# DDC112_Breadboard.net
KiCad netlist of a schematic drawn in Altium Designer
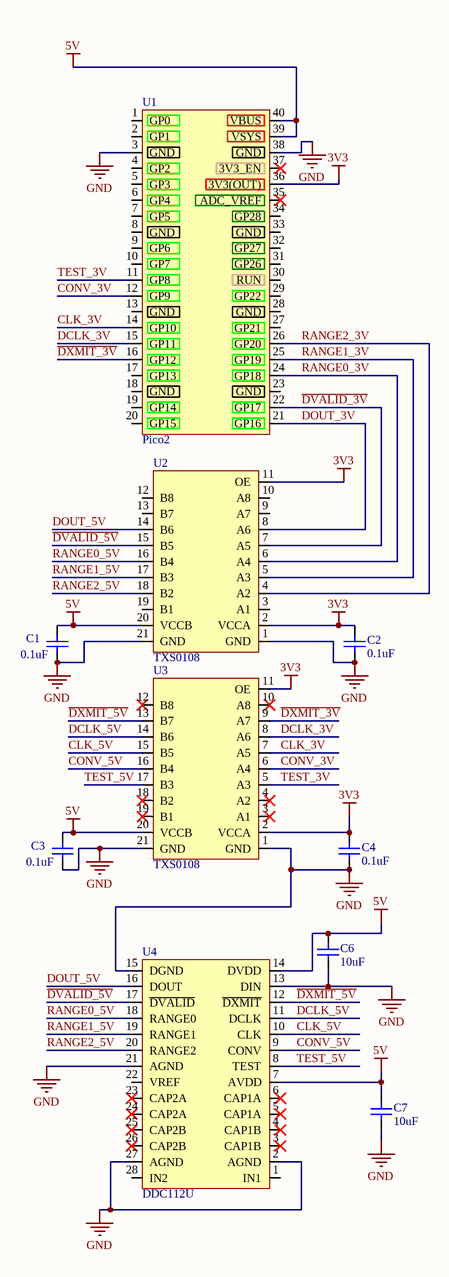
[diagram p0: DDC112_Breadboard.SchDoc]

(export (version "E")
  (design (tool "Eeschema 10.0.6"))
  (components
    (comp (ref "C1")
      (value "0.1uF")
      (description "Cap, Nonpolar, Any, Must choose footprint manually")
      (libsource (lib "DDC112_Components") (part "CAP"))
    )
    (comp (ref "C2")
      (value "0.1uF")
      (description "Cap, Nonpolar, Any, Must choose footprint manually")
      (libsource (lib "DDC112_Components") (part "CAP"))
    )
    (comp (ref "C3")
      (value "0.1uF")
      (description "Cap, Nonpolar, Any, Must choose footprint manually")
      (libsource (lib "DDC112_Components") (part "CAP"))
    )
    (comp (ref "C4")
      (value "0.1uF")
      (description "Cap, Nonpolar, Any, Must choose footprint manually")
      (libsource (lib "DDC112_Components") (part "CAP"))
    )
    (comp (ref "C6")
      (value "10uF")
      (description "Cap, Nonpolar, Any, Must choose footprint manually")
      (libsource (lib "DDC112_Components") (part "CAP"))
    )
    (comp (ref "C7")
      (value "10uF")
      (description "Cap, Nonpolar, Any, Must choose footprint manually")
      (libsource (lib "DDC112_Components") (part "CAP"))
    )
    (comp (ref "U1")
      (value "Pico2")
      (description "Raspberry Pi RP2350 Board 40DIP")
      (libsource (lib "DDC112_Components") (part "Pico2"))
    )
    (comp (ref "U2") (value "TXS0108") (libsource (lib "DDC112_Components") (part "TXS0108")))
    (comp (ref "U3") (value "TXS0108") (libsource (lib "DDC112_Components") (part "TXS0108")))
    (comp (ref "U4")
      (value "DDC112U")
      (description "Dual Current Input 20-Bit ADC 28SOIC")
      (libsource (lib "DDC112_Components") (part "DDC112U"))
    )
  )
  (nets
    (net (code "1") (name "/CLK_3V") (class "Default")
      (node (ref "U1") (pin "14") (pinfunction "GP10_14") (pintype "passive"))
      (node (ref "U3") (pin "7") (pinfunction "A5_7") (pintype "passive"))
    )
    (net (code "2") (name "/CLK_5V") (class "Default")
      (node (ref "U3") (pin "15") (pinfunction "B5_15") (pintype "passive"))
      (node (ref "U4") (pin "10") (pinfunction "CLK_10") (pintype "passive"))
    )
    (net (code "3") (name "/CONV_3V") (class "Default")
      (node (ref "U1") (pin "12") (pinfunction "GP9_12") (pintype "passive"))
      (node (ref "U3") (pin "6") (pinfunction "A4_6") (pintype "passive"))
    )
    (net (code "4") (name "/CONV_5V") (class "Default")
      (node (ref "U3") (pin "16") (pinfunction "B4_16") (pintype "passive"))
      (node (ref "U4") (pin "9") (pinfunction "CONV_9") (pintype "passive"))
    )
    (net (code "5") (name "/DCLK_3V") (class "Default")
      (node (ref "U1") (pin "15") (pinfunction "GP11_15") (pintype "passive"))
      (node (ref "U3") (pin "8") (pinfunction "A6_8") (pintype "passive"))
    )
    (net (code "6") (name "/DCLK_5V") (class "Default")
      (node (ref "U3") (pin "14") (pinfunction "B6_14") (pintype "passive"))
      (node (ref "U4") (pin "11") (pinfunction "DCLK_11") (pintype "passive"))
    )
    (net (code "7") (name "/DOUT_3V") (class "Default")
      (node (ref "U1") (pin "21") (pinfunction "GP16_21") (pintype "passive"))
      (node (ref "U2") (pin "8") (pinfunction "A6_8") (pintype "passive"))
    )
    (net (code "8") (name "/DOUT_5V") (class "Default")
      (node (ref "U2") (pin "14") (pinfunction "B6_14") (pintype "passive"))
      (node (ref "U4") (pin "16") (pinfunction "DOUT_16") (pintype "passive"))
    )
    (net (code "9") (name "/DVALID_3V") (class "Default")
      (node (ref "U1") (pin "22") (pinfunction "GP17_22") (pintype "passive"))
      (node (ref "U2") (pin "7") (pinfunction "A5_7") (pintype "passive"))
    )
    (net (code "10") (name "/DVALID_5V") (class "Default")
      (node (ref "U2") (pin "15") (pinfunction "B5_15") (pintype "passive"))
      (node (ref "U4") (pin "17") (pinfunction "~{DVALID}_17") (pintype "passive"))
    )
    (net (code "11") (name "/DXMIT_3V") (class "Default")
      (node (ref "U1") (pin "16") (pinfunction "GP12_16") (pintype "passive"))
      (node (ref "U3") (pin "9") (pinfunction "A7_9") (pintype "passive"))
    )
    (net (code "12") (name "/DXMIT_5V") (class "Default")
      (node (ref "U3") (pin "13") (pinfunction "B7_13") (pintype "passive"))
      (node (ref "U4") (pin "12") (pinfunction "~{DXMIT}_12") (pintype "passive"))
    )
    (net (code "13") (name "/RANGE0_3V") (class "Default")
      (node (ref "U1") (pin "24") (pinfunction "GP18_24") (pintype "passive"))
      (node (ref "U2") (pin "6") (pinfunction "A4_6") (pintype "passive"))
    )
    (net (code "14") (name "/RANGE0_5V") (class "Default")
      (node (ref "U2") (pin "16") (pinfunction "B4_16") (pintype "passive"))
      (node (ref "U4") (pin "18") (pinfunction "RANGE0_18") (pintype "passive"))
    )
    (net (code "15") (name "/RANGE1_3V") (class "Default")
      (node (ref "U1") (pin "25") (pinfunction "GP19_25") (pintype "passive"))
      (node (ref "U2") (pin "5") (pinfunction "A3_5") (pintype "passive"))
    )
    (net (code "16") (name "/RANGE1_5V") (class "Default")
      (node (ref "U2") (pin "17") (pinfunction "B3_17") (pintype "passive"))
      (node (ref "U4") (pin "19") (pinfunction "RANGE1_19") (pintype "passive"))
    )
    (net (code "17") (name "/RANGE2_3V") (class "Default")
      (node (ref "U1") (pin "26") (pinfunction "GP20_26") (pintype "passive"))
      (node (ref "U2") (pin "4") (pinfunction "A2_4") (pintype "passive"))
    )
    (net (code "18") (name "/RANGE2_5V") (class "Default")
      (node (ref "U2") (pin "18") (pinfunction "B2_18") (pintype "passive"))
      (node (ref "U4") (pin "20") (pinfunction "RANGE2_20") (pintype "passive"))
    )
    (net (code "19") (name "/TEST_3V") (class "Default")
      (node (ref "U1") (pin "11") (pinfunction "GP8_11") (pintype "passive"))
      (node (ref "U3") (pin "5") (pinfunction "A3_5") (pintype "passive"))
    )
    (net (code "20") (name "/TEST_5V") (class "Default")
      (node (ref "U3") (pin "17") (pinfunction "B3_17") (pintype "passive"))
      (node (ref "U4") (pin "8") (pinfunction "TEST_8") (pintype "passive"))
    )
    (net (code "21") (name "3V3") (class "Default")
      (node (ref "C2") (pin "1") (pinfunction "1_1") (pintype "passive"))
      (node (ref "C4") (pin "1") (pinfunction "1_1") (pintype "passive"))
      (node (ref "U1") (pin "36") (pinfunction "3V3(OUT)_36") (pintype "passive"))
      (node (ref "U2") (pin "11") (pinfunction "OE_11") (pintype "passive"))
      (node (ref "U2") (pin "2") (pinfunction "VCCA_2") (pintype "passive"))
      (node (ref "U3") (pin "11") (pinfunction "OE_11") (pintype "passive"))
      (node (ref "U3") (pin "2") (pinfunction "VCCA_2") (pintype "passive"))
    )
    (net (code "22") (name "5V") (class "Default")
      (node (ref "C1") (pin "1") (pinfunction "1_1") (pintype "passive"))
      (node (ref "C3") (pin "1") (pinfunction "1_1") (pintype "passive"))
      (node (ref "C6") (pin "1") (pinfunction "1_1") (pintype "passive"))
      (node (ref "C7") (pin "1") (pinfunction "1_1") (pintype "passive"))
      (node (ref "U1") (pin "39") (pinfunction "VSYS_39") (pintype "passive"))
      (node (ref "U1") (pin "40") (pinfunction "VBUS_40") (pintype "passive"))
      (node (ref "U2") (pin "20") (pinfunction "VCCB_20") (pintype "passive"))
      (node (ref "U3") (pin "20") (pinfunction "VCCB_20") (pintype "passive"))
      (node (ref "U4") (pin "14") (pinfunction "DVDD_14") (pintype "passive"))
      (node (ref "U4") (pin "7") (pinfunction "AVDD_7") (pintype "passive"))
    )
    (net (code "23") (name "GND") (class "Default")
      (node (ref "C1") (pin "2") (pinfunction "2_2") (pintype "passive"))
      (node (ref "C2") (pin "2") (pinfunction "2_2") (pintype "passive"))
      (node (ref "C3") (pin "2") (pinfunction "2_2") (pintype "passive"))
      (node (ref "C4") (pin "2") (pinfunction "2_2") (pintype "passive"))
      (node (ref "C6") (pin "2") (pinfunction "2_2") (pintype "passive"))
      (node (ref "C7") (pin "2") (pinfunction "2_2") (pintype "passive"))
      (node (ref "U1") (pin "3") (pinfunction "GND_3") (pintype "passive"))
      (node (ref "U1") (pin "38") (pinfunction "GND_38") (pintype "passive"))
      (node (ref "U2") (pin "1") (pinfunction "GND_1") (pintype "passive"))
      (node (ref "U2") (pin "21") (pinfunction "GND_21") (pintype "passive"))
      (node (ref "U3") (pin "1") (pinfunction "GND_1") (pintype "passive"))
      (node (ref "U3") (pin "21") (pinfunction "GND_21") (pintype "passive"))
      (node (ref "U4") (pin "13") (pinfunction "DIN_13") (pintype "passive"))
      (node (ref "U4") (pin "15") (pinfunction "DGND_15") (pintype "passive"))
      (node (ref "U4") (pin "2") (pinfunction "AGND_2") (pintype "passive"))
      (node (ref "U4") (pin "21") (pinfunction "AGND_21") (pintype "passive"))
      (node (ref "U4") (pin "27") (pinfunction "AGND_27") (pintype "passive"))
    )
    (net (code "24") (name "unconnected-(U1-3V3_EN-Pad37)") (class "Default")
      (node (ref "U1") (pin "37") (pinfunction "3V3_EN_37") (pintype "passive+no_connect"))
    )
    (net (code "25") (name "unconnected-(U1-ADC_VREF-Pad35)") (class "Default")
      (node (ref "U1") (pin "35") (pinfunction "ADC_VREF_35") (pintype "passive+no_connect"))
    )
    (net (code "26") (name "unconnected-(U1-GND-Pad8)") (class "Default")
      (node (ref "U1") (pin "8") (pinfunction "GND_8") (pintype "passive"))
    )
    (net (code "27") (name "unconnected-(U1-GND-Pad13)") (class "Default")
      (node (ref "U1") (pin "13") (pinfunction "GND_13") (pintype "passive"))
    )
    (net (code "28") (name "unconnected-(U1-GND-Pad18)") (class "Default")
      (node (ref "U1") (pin "18") (pinfunction "GND_18") (pintype "passive"))
    )
    (net (code "29") (name "unconnected-(U1-GND-Pad23)") (class "Default")
      (node (ref "U1") (pin "23") (pinfunction "GND_23") (pintype "passive"))
    )
    (net (code "30") (name "unconnected-(U1-GND-Pad28)") (class "Default")
      (node (ref "U1") (pin "28") (pinfunction "GND_28") (pintype "passive"))
    )
    (net (code "31") (name "unconnected-(U1-GND-Pad33)") (class "Default")
      (node (ref "U1") (pin "33") (pinfunction "GND_33") (pintype "passive"))
    )
    (net (code "32") (name "unconnected-(U1-GP0-Pad1)") (class "Default")
      (node (ref "U1") (pin "1") (pinfunction "GP0_1") (pintype "passive"))
    )
    (net (code "33") (name "unconnected-(U1-GP1-Pad2)") (class "Default")
      (node (ref "U1") (pin "2") (pinfunction "GP1_2") (pintype "passive"))
    )
    (net (code "34") (name "unconnected-(U1-GP2-Pad4)") (class "Default")
      (node (ref "U1") (pin "4") (pinfunction "GP2_4") (pintype "passive"))
    )
    (net (code "35") (name "unconnected-(U1-GP3-Pad5)") (class "Default")
      (node (ref "U1") (pin "5") (pinfunction "GP3_5") (pintype "passive"))
    )
    (net (code "36") (name "unconnected-(U1-GP4-Pad6)") (class "Default")
      (node (ref "U1") (pin "6") (pinfunction "GP4_6") (pintype "passive"))
    )
    (net (code "37") (name "unconnected-(U1-GP5-Pad7)") (class "Default")
      (node (ref "U1") (pin "7") (pinfunction "GP5_7") (pintype "passive"))
    )
    (net (code "38") (name "unconnected-(U1-GP6-Pad9)") (class "Default")
      (node (ref "U1") (pin "9") (pinfunction "GP6_9") (pintype "passive"))
    )
    (net (code "39") (name "unconnected-(U1-GP7-Pad10)") (class "Default")
      (node (ref "U1") (pin "10") (pinfunction "GP7_10") (pintype "passive"))
    )
    (net (code "40") (name "unconnected-(U1-GP13-Pad17)") (class "Default")
      (node (ref "U1") (pin "17") (pinfunction "GP13_17") (pintype "passive"))
    )
    (net (code "41") (name "unconnected-(U1-GP14-Pad19)") (class "Default")
      (node (ref "U1") (pin "19") (pinfunction "GP14_19") (pintype "passive"))
    )
    (net (code "42") (name "unconnected-(U1-GP15-Pad20)") (class "Default")
      (node (ref "U1") (pin "20") (pinfunction "GP15_20") (pintype "passive"))
    )
    (net (code "43") (name "unconnected-(U1-GP21-Pad27)") (class "Default")
      (node (ref "U1") (pin "27") (pinfunction "GP21_27") (pintype "passive"))
    )
    (net (code "44") (name "unconnected-(U1-GP22-Pad29)") (class "Default")
      (node (ref "U1") (pin "29") (pinfunction "GP22_29") (pintype "passive"))
    )
    (net (code "45") (name "unconnected-(U1-GP26-Pad31)") (class "Default")
      (node (ref "U1") (pin "31") (pinfunction "GP26_31") (pintype "passive"))
    )
    (net (code "46") (name "unconnected-(U1-GP27-Pad32)") (class "Default")
      (node (ref "U1") (pin "32") (pinfunction "GP27_32") (pintype "passive"))
    )
    (net (code "47") (name "unconnected-(U1-GP28-Pad34)") (class "Default")
      (node (ref "U1") (pin "34") (pinfunction "GP28_34") (pintype "passive"))
    )
    (net (code "48") (name "unconnected-(U1-RUN-Pad30)") (class "Default")
      (node (ref "U1") (pin "30") (pinfunction "RUN_30") (pintype "passive"))
    )
    (net (code "49") (name "unconnected-(U2-A1-Pad3)") (class "Default")
      (node (ref "U2") (pin "3") (pinfunction "A1_3") (pintype "passive"))
    )
    (net (code "50") (name "unconnected-(U2-A7-Pad9)") (class "Default")
      (node (ref "U2") (pin "9") (pinfunction "A7_9") (pintype "passive"))
    )
    (net (code "51") (name "unconnected-(U2-A8-Pad10)") (class "Default")
      (node (ref "U2") (pin "10") (pinfunction "A8_10") (pintype "passive"))
    )
    (net (code "52") (name "unconnected-(U2-B1-Pad19)") (class "Default")
      (node (ref "U2") (pin "19") (pinfunction "B1_19") (pintype "passive"))
    )
    (net (code "53") (name "unconnected-(U2-B7-Pad13)") (class "Default")
      (node (ref "U2") (pin "13") (pinfunction "B7_13") (pintype "passive"))
    )
    (net (code "54") (name "unconnected-(U2-B8-Pad12)") (class "Default")
      (node (ref "U2") (pin "12") (pinfunction "B8_12") (pintype "passive"))
    )
    (net (code "55") (name "unconnected-(U3-A1-Pad3)") (class "Default")
      (node (ref "U3") (pin "3") (pinfunction "A1_3") (pintype "passive+no_connect"))
    )
    (net (code "56") (name "unconnected-(U3-A2-Pad4)") (class "Default")
      (node (ref "U3") (pin "4") (pinfunction "A2_4") (pintype "passive+no_connect"))
    )
    (net (code "57") (name "unconnected-(U3-A8-Pad10)") (class "Default")
      (node (ref "U3") (pin "10") (pinfunction "A8_10") (pintype "passive+no_connect"))
    )
    (net (code "58") (name "unconnected-(U3-B1-Pad19)") (class "Default")
      (node (ref "U3") (pin "19") (pinfunction "B1_19") (pintype "passive+no_connect"))
    )
    (net (code "59") (name "unconnected-(U3-B2-Pad18)") (class "Default")
      (node (ref "U3") (pin "18") (pinfunction "B2_18") (pintype "passive+no_connect"))
    )
    (net (code "60") (name "unconnected-(U3-B8-Pad12)") (class "Default")
      (node (ref "U3") (pin "12") (pinfunction "B8_12") (pintype "passive+no_connect"))
    )
    (net (code "61") (name "unconnected-(U4-CAP1A-Pad5)") (class "Default")
      (node (ref "U4") (pin "5") (pinfunction "CAP1A_5") (pintype "passive+no_connect"))
    )
    (net (code "62") (name "unconnected-(U4-CAP1A-Pad6)") (class "Default")
      (node (ref "U4") (pin "6") (pinfunction "CAP1A_6") (pintype "passive+no_connect"))
    )
    (net (code "63") (name "unconnected-(U4-CAP1B-Pad3)") (class "Default")
      (node (ref "U4") (pin "3") (pinfunction "CAP1B_3") (pintype "passive+no_connect"))
    )
    (net (code "64") (name "unconnected-(U4-CAP1B-Pad4)") (class "Default")
      (node (ref "U4") (pin "4") (pinfunction "CAP1B_4") (pintype "passive+no_connect"))
    )
    (net (code "65") (name "unconnected-(U4-CAP2A-Pad23)") (class "Default")
      (node (ref "U4") (pin "23") (pinfunction "CAP2A_23") (pintype "passive+no_connect"))
    )
    (net (code "66") (name "unconnected-(U4-CAP2A-Pad24)") (class "Default")
      (node (ref "U4") (pin "24") (pinfunction "CAP2A_24") (pintype "passive+no_connect"))
    )
    (net (code "67") (name "unconnected-(U4-CAP2B-Pad25)") (class "Default")
      (node (ref "U4") (pin "25") (pinfunction "CAP2B_25") (pintype "passive+no_connect"))
    )
    (net (code "68") (name "unconnected-(U4-CAP2B-Pad26)") (class "Default")
      (node (ref "U4") (pin "26") (pinfunction "CAP2B_26") (pintype "passive+no_connect"))
    )
    (net (code "69") (name "unconnected-(U4-IN1-Pad1)") (class "Default")
      (node (ref "U4") (pin "1") (pinfunction "IN1_1") (pintype "passive"))
    )
    (net (code "70") (name "unconnected-(U4-IN2-Pad28)") (class "Default")
      (node (ref "U4") (pin "28") (pinfunction "IN2_28") (pintype "passive"))
    )
    (net (code "71") (name "unconnected-(U4-VREF-Pad22)") (class "Default")
      (node (ref "U4") (pin "22") (pinfunction "VREF_22") (pintype "passive"))
    )
  )
)
